# DaughterBoardInterface.net
KiCad netlist of a schematic drawn in Altium Designer
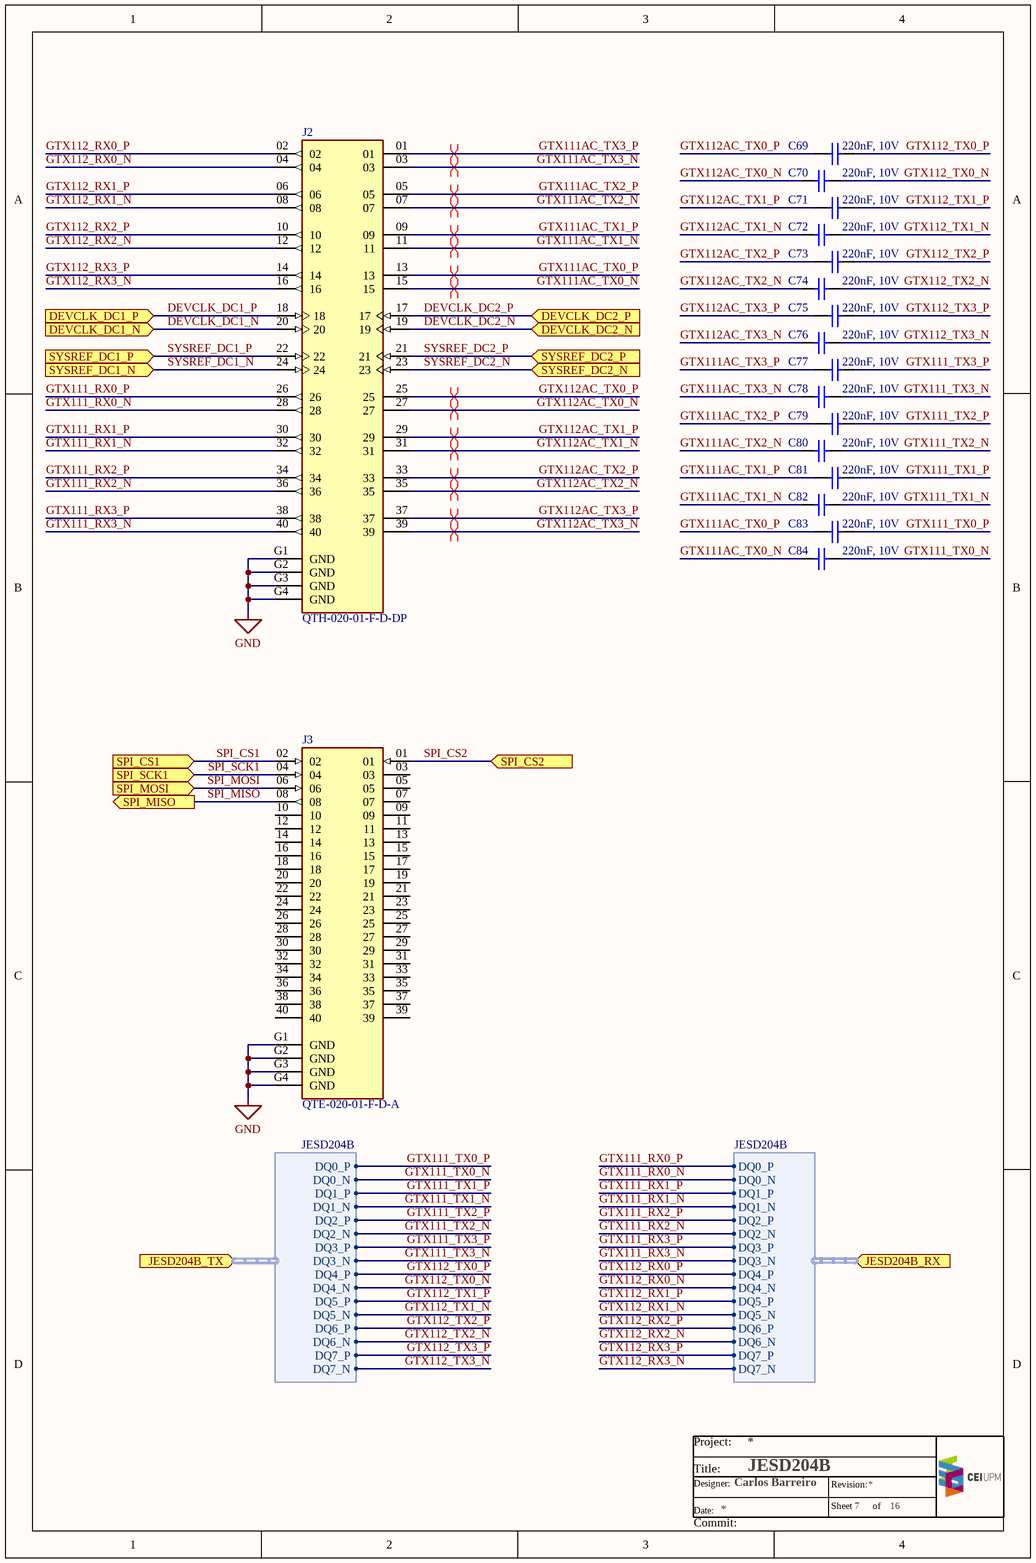
[diagram p0: DaughterBoardInterface.SchDoc]

(export (version "E")
  (design (tool "Eeschema 10.0.6"))
  (components
    (comp (ref "C69")
      (value "220nF, 10V")
      (footprint "WURTH_WCAP-CSGP_0402")
      (description "WCAP-CSGP Multilayer Ceramic Chip Capacitor, General Purpose, size 0402, X5R, 220nF, 10V")
      (fields
        (field (name "MANUFACTURER PART NUMBER") "885012105011")
        (field (name "MANUFACTURER") "Wurth Elektronik")
      )
      (libsource (lib "SpaceVNXBaseBoard") (part "885012105011"))
    )
    (comp (ref "C70")
      (value "220nF, 10V")
      (footprint "WURTH_WCAP-CSGP_0402")
      (description "WCAP-CSGP Multilayer Ceramic Chip Capacitor, General Purpose, size 0402, X5R, 220nF, 10V")
      (fields
        (field (name "MANUFACTURER PART NUMBER") "885012105011")
        (field (name "MANUFACTURER") "Wurth Elektronik")
      )
      (libsource (lib "SpaceVNXBaseBoard") (part "885012105011"))
    )
    (comp (ref "C71")
      (value "220nF, 10V")
      (footprint "WURTH_WCAP-CSGP_0402")
      (description "WCAP-CSGP Multilayer Ceramic Chip Capacitor, General Purpose, size 0402, X5R, 220nF, 10V")
      (fields
        (field (name "MANUFACTURER PART NUMBER") "885012105011")
        (field (name "MANUFACTURER") "Wurth Elektronik")
      )
      (libsource (lib "SpaceVNXBaseBoard") (part "885012105011"))
    )
    (comp (ref "C72")
      (value "220nF, 10V")
      (footprint "WURTH_WCAP-CSGP_0402")
      (description "WCAP-CSGP Multilayer Ceramic Chip Capacitor, General Purpose, size 0402, X5R, 220nF, 10V")
      (fields
        (field (name "MANUFACTURER PART NUMBER") "885012105011")
        (field (name "MANUFACTURER") "Wurth Elektronik")
      )
      (libsource (lib "SpaceVNXBaseBoard") (part "885012105011"))
    )
    (comp (ref "C73")
      (value "220nF, 10V")
      (footprint "WURTH_WCAP-CSGP_0402")
      (description "WCAP-CSGP Multilayer Ceramic Chip Capacitor, General Purpose, size 0402, X5R, 220nF, 10V")
      (fields
        (field (name "MANUFACTURER PART NUMBER") "885012105011")
        (field (name "MANUFACTURER") "Wurth Elektronik")
      )
      (libsource (lib "SpaceVNXBaseBoard") (part "885012105011"))
    )
    (comp (ref "C74")
      (value "220nF, 10V")
      (footprint "WURTH_WCAP-CSGP_0402")
      (description "WCAP-CSGP Multilayer Ceramic Chip Capacitor, General Purpose, size 0402, X5R, 220nF, 10V")
      (fields
        (field (name "MANUFACTURER PART NUMBER") "885012105011")
        (field (name "MANUFACTURER") "Wurth Elektronik")
      )
      (libsource (lib "SpaceVNXBaseBoard") (part "885012105011"))
    )
    (comp (ref "C75")
      (value "220nF, 10V")
      (footprint "WURTH_WCAP-CSGP_0402")
      (description "WCAP-CSGP Multilayer Ceramic Chip Capacitor, General Purpose, size 0402, X5R, 220nF, 10V")
      (fields
        (field (name "MANUFACTURER PART NUMBER") "885012105011")
        (field (name "MANUFACTURER") "Wurth Elektronik")
      )
      (libsource (lib "SpaceVNXBaseBoard") (part "885012105011"))
    )
    (comp (ref "C76")
      (value "220nF, 10V")
      (footprint "WURTH_WCAP-CSGP_0402")
      (description "WCAP-CSGP Multilayer Ceramic Chip Capacitor, General Purpose, size 0402, X5R, 220nF, 10V")
      (fields
        (field (name "MANUFACTURER PART NUMBER") "885012105011")
        (field (name "MANUFACTURER") "Wurth Elektronik")
      )
      (libsource (lib "SpaceVNXBaseBoard") (part "885012105011"))
    )
    (comp (ref "C77")
      (value "220nF, 10V")
      (footprint "WURTH_WCAP-CSGP_0402")
      (description "WCAP-CSGP Multilayer Ceramic Chip Capacitor, General Purpose, size 0402, X5R, 220nF, 10V")
      (fields
        (field (name "MANUFACTURER PART NUMBER") "885012105011")
        (field (name "MANUFACTURER") "Wurth Elektronik")
      )
      (libsource (lib "SpaceVNXBaseBoard") (part "885012105011"))
    )
    (comp (ref "C78")
      (value "220nF, 10V")
      (footprint "WURTH_WCAP-CSGP_0402")
      (description "WCAP-CSGP Multilayer Ceramic Chip Capacitor, General Purpose, size 0402, X5R, 220nF, 10V")
      (fields
        (field (name "MANUFACTURER PART NUMBER") "885012105011")
        (field (name "MANUFACTURER") "Wurth Elektronik")
      )
      (libsource (lib "SpaceVNXBaseBoard") (part "885012105011"))
    )
    (comp (ref "C79")
      (value "220nF, 10V")
      (footprint "WURTH_WCAP-CSGP_0402")
      (description "WCAP-CSGP Multilayer Ceramic Chip Capacitor, General Purpose, size 0402, X5R, 220nF, 10V")
      (fields
        (field (name "MANUFACTURER PART NUMBER") "885012105011")
        (field (name "MANUFACTURER") "Wurth Elektronik")
      )
      (libsource (lib "SpaceVNXBaseBoard") (part "885012105011"))
    )
    (comp (ref "C80")
      (value "220nF, 10V")
      (footprint "WURTH_WCAP-CSGP_0402")
      (description "WCAP-CSGP Multilayer Ceramic Chip Capacitor, General Purpose, size 0402, X5R, 220nF, 10V")
      (fields
        (field (name "MANUFACTURER PART NUMBER") "885012105011")
        (field (name "MANUFACTURER") "Wurth Elektronik")
      )
      (libsource (lib "SpaceVNXBaseBoard") (part "885012105011"))
    )
    (comp (ref "C81")
      (value "220nF, 10V")
      (footprint "WURTH_WCAP-CSGP_0402")
      (description "WCAP-CSGP Multilayer Ceramic Chip Capacitor, General Purpose, size 0402, X5R, 220nF, 10V")
      (fields
        (field (name "MANUFACTURER PART NUMBER") "885012105011")
        (field (name "MANUFACTURER") "Wurth Elektronik")
      )
      (libsource (lib "SpaceVNXBaseBoard") (part "885012105011"))
    )
    (comp (ref "C82")
      (value "220nF, 10V")
      (footprint "WURTH_WCAP-CSGP_0402")
      (description "WCAP-CSGP Multilayer Ceramic Chip Capacitor, General Purpose, size 0402, X5R, 220nF, 10V")
      (fields
        (field (name "MANUFACTURER PART NUMBER") "885012105011")
        (field (name "MANUFACTURER") "Wurth Elektronik")
      )
      (libsource (lib "SpaceVNXBaseBoard") (part "885012105011"))
    )
    (comp (ref "C83")
      (value "220nF, 10V")
      (footprint "WURTH_WCAP-CSGP_0402")
      (description "WCAP-CSGP Multilayer Ceramic Chip Capacitor, General Purpose, size 0402, X5R, 220nF, 10V")
      (fields
        (field (name "MANUFACTURER PART NUMBER") "885012105011")
        (field (name "MANUFACTURER") "Wurth Elektronik")
      )
      (libsource (lib "SpaceVNXBaseBoard") (part "885012105011"))
    )
    (comp (ref "C84")
      (value "220nF, 10V")
      (footprint "WURTH_WCAP-CSGP_0402")
      (description "WCAP-CSGP Multilayer Ceramic Chip Capacitor, General Purpose, size 0402, X5R, 220nF, 10V")
      (fields
        (field (name "MANUFACTURER PART NUMBER") "885012105011")
        (field (name "MANUFACTURER") "Wurth Elektronik")
      )
      (libsource (lib "SpaceVNXBaseBoard") (part "885012105011"))
    )
    (comp (ref "J2")
      (value "QTH-020-01-F-D-DP")
      (footprint "SAMTEC_QTH-020-01-X-D-DP-A")
      (description "0.50 mm Q Pairs® High-Speed Ground Plane Terminal Strip, Differential Pair")
      (fields (field (name "MF") "Samtec"))
      (libsource (lib "SpaceVNXBaseBoard") (part "QTH-020-01-F-D-DP"))
    )
    (comp (ref "J3")
      (value "QTE-020-01-F-D-A")
      (footprint "SAMTEC_QTE-020-01-X-D-A")
      (description "40 Position Connector Header, Outer Shroud Contacts Surface Mount Gold")
      (fields (field (name "MF") "Samtec"))
      (libsource (lib "SpaceVNXBaseBoard") (part "QTE-020-01-F-D-A"))
    )
  )
  (nets
    (net (code "2") (name "/DEVCLK_DC1_N") (class "Default")
      (node (ref "J2") (pin "20") (pinfunction "20_20") (pintype "input"))
    )
    (net (code "3") (name "/DEVCLK_DC1_P") (class "Default")
      (node (ref "J2") (pin "18") (pinfunction "18_18") (pintype "input"))
    )
    (net (code "4") (name "/DEVCLK_DC2_N") (class "Default")
      (node (ref "J2") (pin "19") (pinfunction "19_19") (pintype "input"))
    )
    (net (code "5") (name "/DEVCLK_DC2_P") (class "Default")
      (node (ref "J2") (pin "17") (pinfunction "17_17") (pintype "input"))
    )
    (net (code "6") (name "/GTX111AC_TX0_N") (class "Default")
      (node (ref "C84") (pin "1") (pinfunction "1_1") (pintype "passive"))
      (node (ref "J2") (pin "15") (pinfunction "15_15") (pintype "passive"))
    )
    (net (code "7") (name "/GTX111AC_TX0_P") (class "Default")
      (node (ref "C83") (pin "1") (pinfunction "1_1") (pintype "passive"))
      (node (ref "J2") (pin "13") (pinfunction "13_13") (pintype "passive"))
    )
    (net (code "8") (name "/GTX111AC_TX1_N") (class "Default")
      (node (ref "C82") (pin "1") (pinfunction "1_1") (pintype "passive"))
      (node (ref "J2") (pin "11") (pinfunction "11_11") (pintype "passive"))
    )
    (net (code "9") (name "/GTX111AC_TX1_P") (class "Default")
      (node (ref "C81") (pin "1") (pinfunction "1_1") (pintype "passive"))
      (node (ref "J2") (pin "09") (pinfunction "09_09") (pintype "passive"))
    )
    (net (code "10") (name "/GTX111AC_TX2_N") (class "Default")
      (node (ref "C80") (pin "1") (pinfunction "1_1") (pintype "passive"))
      (node (ref "J2") (pin "07") (pinfunction "07_07") (pintype "passive"))
    )
    (net (code "11") (name "/GTX111AC_TX2_P") (class "Default")
      (node (ref "C79") (pin "1") (pinfunction "1_1") (pintype "passive"))
      (node (ref "J2") (pin "05") (pinfunction "05_05") (pintype "passive"))
    )
    (net (code "12") (name "/GTX111AC_TX3_N") (class "Default")
      (node (ref "C78") (pin "1") (pinfunction "1_1") (pintype "passive"))
      (node (ref "J2") (pin "03") (pinfunction "03_03") (pintype "passive"))
    )
    (net (code "13") (name "/GTX111AC_TX3_P") (class "Default")
      (node (ref "C77") (pin "1") (pinfunction "1_1") (pintype "passive"))
      (node (ref "J2") (pin "01") (pinfunction "01_01") (pintype "passive"))
    )
    (net (code "14") (name "/GTX111_RX0_N") (class "Default")
      (node (ref "J2") (pin "28") (pinfunction "28_28") (pintype "output"))
    )
    (net (code "15") (name "/GTX111_RX0_P") (class "Default")
      (node (ref "J2") (pin "26") (pinfunction "26_26") (pintype "output"))
    )
    (net (code "16") (name "/GTX111_RX1_N") (class "Default")
      (node (ref "J2") (pin "32") (pinfunction "32_32") (pintype "output"))
    )
    (net (code "17") (name "/GTX111_RX1_P") (class "Default")
      (node (ref "J2") (pin "30") (pinfunction "30_30") (pintype "output"))
    )
    (net (code "18") (name "/GTX111_RX2_N") (class "Default")
      (node (ref "J2") (pin "36") (pinfunction "36_36") (pintype "output"))
    )
    (net (code "19") (name "/GTX111_RX2_P") (class "Default")
      (node (ref "J2") (pin "34") (pinfunction "34_34") (pintype "output"))
    )
    (net (code "20") (name "/GTX111_RX3_N") (class "Default")
      (node (ref "J2") (pin "40") (pinfunction "40_40") (pintype "output"))
    )
    (net (code "21") (name "/GTX111_RX3_P") (class "Default")
      (node (ref "J2") (pin "38") (pinfunction "38_38") (pintype "output"))
    )
    (net (code "22") (name "/GTX111_TX0_N") (class "Default")
      (node (ref "C84") (pin "2") (pinfunction "2_2") (pintype "passive"))
    )
    (net (code "23") (name "/GTX111_TX0_P") (class "Default")
      (node (ref "C83") (pin "2") (pinfunction "2_2") (pintype "passive"))
    )
    (net (code "24") (name "/GTX111_TX1_N") (class "Default")
      (node (ref "C82") (pin "2") (pinfunction "2_2") (pintype "passive"))
    )
    (net (code "25") (name "/GTX111_TX1_P") (class "Default")
      (node (ref "C81") (pin "2") (pinfunction "2_2") (pintype "passive"))
    )
    (net (code "26") (name "/GTX111_TX2_N") (class "Default")
      (node (ref "C80") (pin "2") (pinfunction "2_2") (pintype "passive"))
    )
    (net (code "27") (name "/GTX111_TX2_P") (class "Default")
      (node (ref "C79") (pin "2") (pinfunction "2_2") (pintype "passive"))
    )
    (net (code "28") (name "/GTX111_TX3_N") (class "Default")
      (node (ref "C78") (pin "2") (pinfunction "2_2") (pintype "passive"))
    )
    (net (code "29") (name "/GTX111_TX3_P") (class "Default")
      (node (ref "C77") (pin "2") (pinfunction "2_2") (pintype "passive"))
    )
    (net (code "30") (name "/GTX112AC_TX0_N") (class "Default")
      (node (ref "C70") (pin "1") (pinfunction "1_1") (pintype "passive"))
      (node (ref "J2") (pin "27") (pinfunction "27_27") (pintype "passive"))
    )
    (net (code "31") (name "/GTX112AC_TX0_P") (class "Default")
      (node (ref "C69") (pin "1") (pinfunction "1_1") (pintype "passive"))
      (node (ref "J2") (pin "25") (pinfunction "25_25") (pintype "passive"))
    )
    (net (code "32") (name "/GTX112AC_TX1_N") (class "Default")
      (node (ref "C72") (pin "1") (pinfunction "1_1") (pintype "passive"))
      (node (ref "J2") (pin "31") (pinfunction "31_31") (pintype "passive"))
    )
    (net (code "33") (name "/GTX112AC_TX1_P") (class "Default")
      (node (ref "C71") (pin "1") (pinfunction "1_1") (pintype "passive"))
      (node (ref "J2") (pin "29") (pinfunction "29_29") (pintype "passive"))
    )
    (net (code "34") (name "/GTX112AC_TX2_N") (class "Default")
      (node (ref "C74") (pin "1") (pinfunction "1_1") (pintype "passive"))
      (node (ref "J2") (pin "35") (pinfunction "35_35") (pintype "passive"))
    )
    (net (code "35") (name "/GTX112AC_TX2_P") (class "Default")
      (node (ref "C73") (pin "1") (pinfunction "1_1") (pintype "passive"))
      (node (ref "J2") (pin "33") (pinfunction "33_33") (pintype "passive"))
    )
    (net (code "36") (name "/GTX112AC_TX3_N") (class "Default")
      (node (ref "C76") (pin "1") (pinfunction "1_1") (pintype "passive"))
      (node (ref "J2") (pin "39") (pinfunction "39_39") (pintype "passive"))
    )
    (net (code "37") (name "/GTX112AC_TX3_P") (class "Default")
      (node (ref "C75") (pin "1") (pinfunction "1_1") (pintype "passive"))
      (node (ref "J2") (pin "37") (pinfunction "37_37") (pintype "passive"))
    )
    (net (code "38") (name "/GTX112_RX0_N") (class "Default")
      (node (ref "J2") (pin "04") (pinfunction "04_04") (pintype "output"))
    )
    (net (code "39") (name "/GTX112_RX0_P") (class "Default")
      (node (ref "J2") (pin "02") (pinfunction "02_02") (pintype "output"))
    )
    (net (code "40") (name "/GTX112_RX1_N") (class "Default")
      (node (ref "J2") (pin "08") (pinfunction "08_08") (pintype "output"))
    )
    (net (code "41") (name "/GTX112_RX1_P") (class "Default")
      (node (ref "J2") (pin "06") (pinfunction "06_06") (pintype "output"))
    )
    (net (code "42") (name "/GTX112_RX2_N") (class "Default")
      (node (ref "J2") (pin "12") (pinfunction "12_12") (pintype "output"))
    )
    (net (code "43") (name "/GTX112_RX2_P") (class "Default")
      (node (ref "J2") (pin "10") (pinfunction "10_10") (pintype "output"))
    )
    (net (code "44") (name "/GTX112_RX3_N") (class "Default")
      (node (ref "J2") (pin "16") (pinfunction "16_16") (pintype "output"))
    )
    (net (code "45") (name "/GTX112_RX3_P") (class "Default")
      (node (ref "J2") (pin "14") (pinfunction "14_14") (pintype "output"))
    )
    (net (code "46") (name "/GTX112_TX0_N") (class "Default")
      (node (ref "C70") (pin "2") (pinfunction "2_2") (pintype "passive"))
    )
    (net (code "47") (name "/GTX112_TX0_P") (class "Default")
      (node (ref "C69") (pin "2") (pinfunction "2_2") (pintype "passive"))
    )
    (net (code "48") (name "/GTX112_TX1_N") (class "Default")
      (node (ref "C72") (pin "2") (pinfunction "2_2") (pintype "passive"))
    )
    (net (code "49") (name "/GTX112_TX1_P") (class "Default")
      (node (ref "C71") (pin "2") (pinfunction "2_2") (pintype "passive"))
    )
    (net (code "50") (name "/GTX112_TX2_N") (class "Default")
      (node (ref "C74") (pin "2") (pinfunction "2_2") (pintype "passive"))
    )
    (net (code "51") (name "/GTX112_TX2_P") (class "Default")
      (node (ref "C73") (pin "2") (pinfunction "2_2") (pintype "passive"))
    )
    (net (code "52") (name "/GTX112_TX3_N") (class "Default")
      (node (ref "C76") (pin "2") (pinfunction "2_2") (pintype "passive"))
    )
    (net (code "53") (name "/GTX112_TX3_P") (class "Default")
      (node (ref "C75") (pin "2") (pinfunction "2_2") (pintype "passive"))
    )
    (net (code "54") (name "/SPI_CS1") (class "Default")
      (node (ref "J3") (pin "02") (pinfunction "02_02") (pintype "input"))
    )
    (net (code "55") (name "/SPI_CS2") (class "Default")
      (node (ref "J3") (pin "01") (pinfunction "01_01") (pintype "input"))
    )
    (net (code "56") (name "/SPI_MISO") (class "Default")
      (node (ref "J3") (pin "08") (pinfunction "08_08") (pintype "output"))
    )
    (net (code "57") (name "/SPI_MOSI") (class "Default")
      (node (ref "J3") (pin "06") (pinfunction "06_06") (pintype "input"))
    )
    (net (code "58") (name "/SPI_SCK1") (class "Default")
      (node (ref "J3") (pin "04") (pinfunction "04_04") (pintype "input"))
    )
    (net (code "59") (name "/SYSREF_DC1_N") (class "Default")
      (node (ref "J2") (pin "24") (pinfunction "24_24") (pintype "input"))
    )
    (net (code "60") (name "/SYSREF_DC1_P") (class "Default")
      (node (ref "J2") (pin "22") (pinfunction "22_22") (pintype "input"))
    )
    (net (code "61") (name "/SYSREF_DC2_N") (class "Default")
      (node (ref "J2") (pin "23") (pinfunction "23_23") (pintype "input"))
    )
    (net (code "62") (name "/SYSREF_DC2_P") (class "Default")
      (node (ref "J2") (pin "21") (pinfunction "21_21") (pintype "input"))
    )
    (net (code "64") (name "GND") (class "Default")
      (node (ref "J2") (pin "G1") (pinfunction "GND_G1") (pintype "power_in"))
      (node (ref "J2") (pin "G2") (pinfunction "GND_G2") (pintype "power_in"))
      (node (ref "J2") (pin "G3") (pinfunction "GND_G3") (pintype "power_in"))
      (node (ref "J2") (pin "G4") (pinfunction "GND_G4") (pintype "power_in"))
      (node (ref "J3") (pin "G1") (pinfunction "GND_G1") (pintype "power_in"))
      (node (ref "J3") (pin "G2") (pinfunction "GND_G2") (pintype "power_in"))
      (node (ref "J3") (pin "G3") (pinfunction "GND_G3") (pintype "power_in"))
      (node (ref "J3") (pin "G4") (pinfunction "GND_G4") (pintype "power_in"))
    )
    (net (code "65") (name "unconnected-(J3-Pad03)") (class "Default")
      (node (ref "J3") (pin "03") (pinfunction "03_03") (pintype "passive"))
    )
    (net (code "66") (name "unconnected-(J3-Pad05)") (class "Default")
      (node (ref "J3") (pin "05") (pinfunction "05_05") (pintype "passive"))
    )
    (net (code "67") (name "unconnected-(J3-Pad07)") (class "Default")
      (node (ref "J3") (pin "07") (pinfunction "07_07") (pintype "passive"))
    )
    (net (code "68") (name "unconnected-(J3-Pad09)") (class "Default")
      (node (ref "J3") (pin "09") (pinfunction "09_09") (pintype "passive"))
    )
    (net (code "69") (name "unconnected-(J3-Pad10)") (class "Default")
      (node (ref "J3") (pin "10") (pinfunction "10_10") (pintype "passive"))
    )
    (net (code "70") (name "unconnected-(J3-Pad11)") (class "Default")
      (node (ref "J3") (pin "11") (pinfunction "11_11") (pintype "passive"))
    )
    (net (code "71") (name "unconnected-(J3-Pad12)") (class "Default")
      (node (ref "J3") (pin "12") (pinfunction "12_12") (pintype "passive"))
    )
    (net (code "72") (name "unconnected-(J3-Pad13)") (class "Default")
      (node (ref "J3") (pin "13") (pinfunction "13_13") (pintype "passive"))
    )
    (net (code "73") (name "unconnected-(J3-Pad14)") (class "Default")
      (node (ref "J3") (pin "14") (pinfunction "14_14") (pintype "passive"))
    )
    (net (code "74") (name "unconnected-(J3-Pad15)") (class "Default")
      (node (ref "J3") (pin "15") (pinfunction "15_15") (pintype "passive"))
    )
    (net (code "75") (name "unconnected-(J3-Pad16)") (class "Default")
      (node (ref "J3") (pin "16") (pinfunction "16_16") (pintype "passive"))
    )
    (net (code "76") (name "unconnected-(J3-Pad17)") (class "Default")
      (node (ref "J3") (pin "17") (pinfunction "17_17") (pintype "passive"))
    )
    (net (code "77") (name "unconnected-(J3-Pad18)") (class "Default")
      (node (ref "J3") (pin "18") (pinfunction "18_18") (pintype "passive"))
    )
    (net (code "78") (name "unconnected-(J3-Pad19)") (class "Default")
      (node (ref "J3") (pin "19") (pinfunction "19_19") (pintype "passive"))
    )
    (net (code "79") (name "unconnected-(J3-Pad20)") (class "Default")
      (node (ref "J3") (pin "20") (pinfunction "20_20") (pintype "passive"))
    )
    (net (code "80") (name "unconnected-(J3-Pad21)") (class "Default")
      (node (ref "J3") (pin "21") (pinfunction "21_21") (pintype "passive"))
    )
    (net (code "81") (name "unconnected-(J3-Pad22)") (class "Default")
      (node (ref "J3") (pin "22") (pinfunction "22_22") (pintype "passive"))
    )
    (net (code "82") (name "unconnected-(J3-Pad23)") (class "Default")
      (node (ref "J3") (pin "23") (pinfunction "23_23") (pintype "passive"))
    )
    (net (code "83") (name "unconnected-(J3-Pad24)") (class "Default")
      (node (ref "J3") (pin "24") (pinfunction "24_24") (pintype "passive"))
    )
    (net (code "84") (name "unconnected-(J3-Pad25)") (class "Default")
      (node (ref "J3") (pin "25") (pinfunction "25_25") (pintype "passive"))
    )
    (net (code "85") (name "unconnected-(J3-Pad26)") (class "Default")
      (node (ref "J3") (pin "26") (pinfunction "26_26") (pintype "passive"))
    )
    (net (code "86") (name "unconnected-(J3-Pad27)") (class "Default")
      (node (ref "J3") (pin "27") (pinfunction "27_27") (pintype "passive"))
    )
    (net (code "87") (name "unconnected-(J3-Pad28)") (class "Default")
      (node (ref "J3") (pin "28") (pinfunction "28_28") (pintype "passive"))
    )
    (net (code "88") (name "unconnected-(J3-Pad29)") (class "Default")
      (node (ref "J3") (pin "29") (pinfunction "29_29") (pintype "passive"))
    )
    (net (code "89") (name "unconnected-(J3-Pad30)") (class "Default")
      (node (ref "J3") (pin "30") (pinfunction "30_30") (pintype "passive"))
    )
    (net (code "90") (name "unconnected-(J3-Pad31)") (class "Default")
      (node (ref "J3") (pin "31") (pinfunction "31_31") (pintype "passive"))
    )
    (net (code "91") (name "unconnected-(J3-Pad32)") (class "Default")
      (node (ref "J3") (pin "32") (pinfunction "32_32") (pintype "passive"))
    )
    (net (code "92") (name "unconnected-(J3-Pad33)") (class "Default")
      (node (ref "J3") (pin "33") (pinfunction "33_33") (pintype "passive"))
    )
    (net (code "93") (name "unconnected-(J3-Pad34)") (class "Default")
      (node (ref "J3") (pin "34") (pinfunction "34_34") (pintype "passive"))
    )
    (net (code "94") (name "unconnected-(J3-Pad35)") (class "Default")
      (node (ref "J3") (pin "35") (pinfunction "35_35") (pintype "passive"))
    )
    (net (code "95") (name "unconnected-(J3-Pad36)") (class "Default")
      (node (ref "J3") (pin "36") (pinfunction "36_36") (pintype "passive"))
    )
    (net (code "96") (name "unconnected-(J3-Pad37)") (class "Default")
      (node (ref "J3") (pin "37") (pinfunction "37_37") (pintype "passive"))
    )
    (net (code "97") (name "unconnected-(J3-Pad38)") (class "Default")
      (node (ref "J3") (pin "38") (pinfunction "38_38") (pintype "passive"))
    )
    (net (code "98") (name "unconnected-(J3-Pad39)") (class "Default")
      (node (ref "J3") (pin "39") (pinfunction "39_39") (pintype "passive"))
    )
    (net (code "99") (name "unconnected-(J3-Pad40)") (class "Default")
      (node (ref "J3") (pin "40") (pinfunction "40_40") (pintype "passive"))
    )
  )
)
